# AOP_Decoupling.net
KiCad netlist of a schematic drawn in Altium Designer
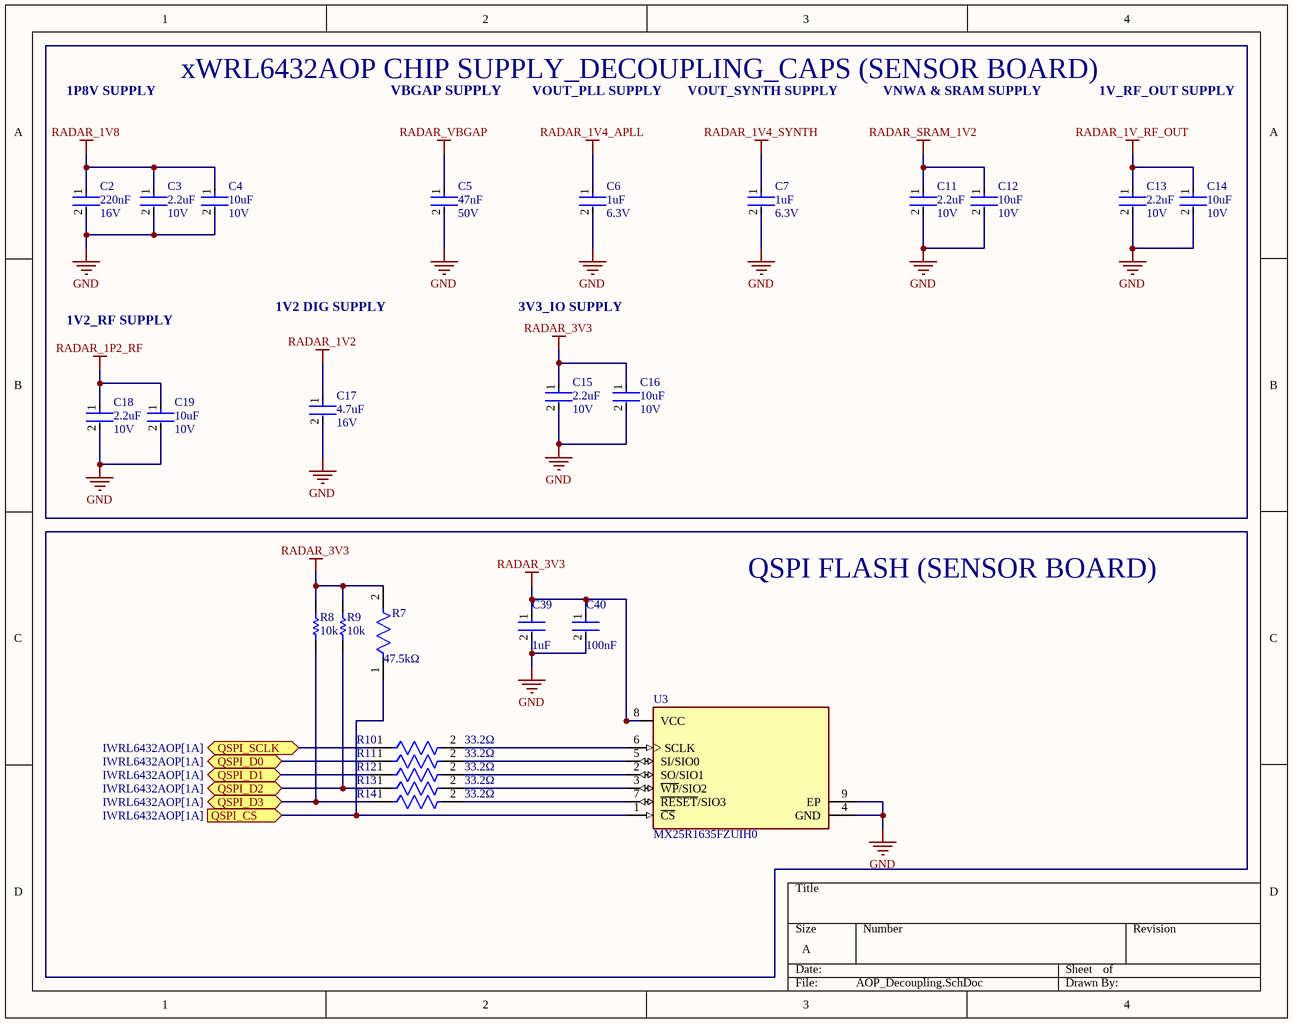
[diagram p0: AOP_Decoupling.SchDoc]

(export (version "E")
  (design (tool "Eeschema 10.0.6"))
  (components
    (comp (ref "C2")
      (value "GRM155R71C224KA12D")
      (footprint "FP-GRM155-0_05-IPC_C")
      (description "Chip Multilayer Ceramic Capacitors for General Purpose, 0402, 0.22uF, X7R, 15%, 10%, 16V")
      (fields
        (field (name "CAPACITANCE") "220nF")
        (field (name "VOLTAGE") "16V")
        (field (name "TOLERANCE") "10%")
      )
      (libsource (lib "Altium Content Vault") (part "02cd4be3c70576c341d710602a673aa"))
    )
    (comp (ref "C3")
      (value "GRM155R61A225ME01D")
      (footprint "FP-GRM155-0_05-IPC_A")
      (description "Chip Multilayer Ceramic Capacitors for General Purpose, 0402, 2.2uF, X5R, 15%, 20%, 10V")
      (fields (field (name "CAPACITANCE") "2.2uF") (field (name "VOLTAGE") "10V"))
      (libsource (lib "Altium Content Vault") (part "02cd4be3c70576c341d710602a673aa"))
    )
    (comp (ref "C4")
      (value "GRM188Z71A106MA73D")
      (footprint "FP-GRM188-0_2-IPC_B")
      (description "Chip Multilayer Ceramic Capacitors for General Purpose, 0603, 10uF, X7R, 15%, 20%, 10V")
      (fields (field (name "VOLTAGE") "10V") (field (name "CAPACITANCE") "10uF"))
      (libsource (lib "Altium Content Vault") (part "11868f565c42a9108669ba33697ecf6"))
    )
    (comp (ref "C5")
      (value "C1005X7R1H473K050BB")
      (footprint "FP-C1005-050-0_05-IPC_C")
      (description "Multilayer Ceramic Capacitors 47nF ±10% 50V X7R SMD 0402")
      (fields
        (field (name "VOLTAGE") "50V")
        (field (name "CAPACITANCE") "47nF")
        (field (name "VOLTAGE RATING (DC)") "50V")
        (field (name "TOLERANCE") "10%")
      )
      (libsource (lib "Altium Content Vault") (part "b4654b650e69147ec39a6b967a45e02"))
    )
    (comp (ref "C6")
      (value "GRM155R70J105KA12D")
      (footprint "FP-GRM155-0_05-MFG")
      (description "Chip Multilayer Ceramic Capacitors for General Purpose, 0402, 1.0uF, X7R, 15%, 10%, 6.3V")
      (fields
        (field (name "CAPACITANCE") "1uF")
        (field (name "TOLERANCE") "10%")
        (field (name "VOLTAGE RATING") "6.3V")
      )
      (libsource (lib "Altium Content Vault") (part "02cd4be3c70576c341d710602a673aa"))
    )
    (comp (ref "C7")
      (value "GRM155R70J105KA12D")
      (footprint "FP-GRM155-0_05-MFG")
      (description "Chip Multilayer Ceramic Capacitors for General Purpose, 0402, 1.0uF, X7R, 15%, 10%, 6.3V")
      (fields
        (field (name "CAPACITANCE") "1uF")
        (field (name "TOLERANCE") "10%")
        (field (name "VOLTAGE RATING") "6.3V")
      )
      (libsource (lib "Altium Content Vault") (part "02cd4be3c70576c341d710602a673aa"))
    )
    (comp (ref "C11")
      (value "GRM155R61A225ME01D")
      (footprint "FP-GRM155-0_05-IPC_A")
      (description "Chip Multilayer Ceramic Capacitors for General Purpose, 0402, 2.2uF, X5R, 15%, 20%, 10V")
      (fields (field (name "CAPACITANCE") "2.2uF") (field (name "VOLTAGE") "10V"))
      (libsource (lib "Altium Content Vault") (part "02cd4be3c70576c341d710602a673aa"))
    )
    (comp (ref "C12")
      (value "GRM188Z71A106MA73D")
      (footprint "FP-GRM188-0_2-IPC_B")
      (description "Chip Multilayer Ceramic Capacitors for General Purpose, 0603, 10uF, X7R, 15%, 20%, 10V")
      (fields (field (name "VOLTAGE") "10V") (field (name "CAPACITANCE") "10uF"))
      (libsource (lib "Altium Content Vault") (part "11868f565c42a9108669ba33697ecf6"))
    )
    (comp (ref "C13")
      (value "GRM155R61A225ME01D")
      (footprint "FP-GRM155-0_05-IPC_A")
      (description "Chip Multilayer Ceramic Capacitors for General Purpose, 0402, 2.2uF, X5R, 15%, 20%, 10V")
      (fields (field (name "CAPACITANCE") "2.2uF") (field (name "VOLTAGE") "10V"))
      (libsource (lib "Altium Content Vault") (part "02cd4be3c70576c341d710602a673aa"))
    )
    (comp (ref "C14")
      (value "GRM188Z71A106MA73D")
      (footprint "FP-GRM188-0_2-IPC_B")
      (description "Chip Multilayer Ceramic Capacitors for General Purpose, 0603, 10uF, X7R, 15%, 20%, 10V")
      (fields (field (name "VOLTAGE") "10V") (field (name "CAPACITANCE") "10uF"))
      (libsource (lib "Altium Content Vault") (part "11868f565c42a9108669ba33697ecf6"))
    )
    (comp (ref "C15")
      (value "GRM155R61A225ME01D")
      (footprint "FP-GRM155-0_05-IPC_A")
      (description "Chip Multilayer Ceramic Capacitors for General Purpose, 0402, 2.2uF, X5R, 15%, 20%, 10V")
      (fields (field (name "CAPACITANCE") "2.2uF") (field (name "VOLTAGE") "10V"))
      (libsource (lib "Altium Content Vault") (part "02cd4be3c70576c341d710602a673aa"))
    )
    (comp (ref "C16")
      (value "GRM188Z71A106MA73D")
      (footprint "FP-GRM188-0_2-IPC_B")
      (description "Chip Multilayer Ceramic Capacitors for General Purpose, 0603, 10uF, X7R, 15%, 20%, 10V")
      (fields (field (name "VOLTAGE") "10V") (field (name "CAPACITANCE") "10uF"))
      (libsource (lib "Altium Content Vault") (part "11868f565c42a9108669ba33697ecf6"))
    )
    (comp (ref "C17")
      (value "GCJ21BR71C475KA01L")
      (footprint "FP-GCJ21B-0_3-IPC_C")
      (description "Multilayer Ceramic Capacitors MLCC - SMD/SMT 0805 4.7uF 10%, 16VDC,  X7R 15%")
      (fields
        (field (name "VOLTAGE RATING (DC)") "16V")
        (field (name "CAPACITANCE") "4.7uF")
        (field (name "TOLERANCE") "10%")
      )
      (libsource (lib "Altium Content Vault") (part "02cd4be3c70576c341d710602a673aa"))
    )
    (comp (ref "C18")
      (value "GRM155R61A225ME01D")
      (footprint "FP-GRM155-0_05-IPC_A")
      (description "Chip Multilayer Ceramic Capacitors for General Purpose, 0402, 2.2uF, X5R, 15%, 20%, 10V")
      (fields (field (name "CAPACITANCE") "2.2uF") (field (name "VOLTAGE") "10V"))
      (libsource (lib "Altium Content Vault") (part "02cd4be3c70576c341d710602a673aa"))
    )
    (comp (ref "C19")
      (value "GRM188Z71A106MA73D")
      (footprint "FP-GRM188-0_2-IPC_B")
      (description "Chip Multilayer Ceramic Capacitors for General Purpose, 0603, 10uF, X7R, 15%, 20%, 10V")
      (fields (field (name "VOLTAGE") "10V") (field (name "CAPACITANCE") "10uF"))
      (libsource (lib "Altium Content Vault") (part "11868f565c42a9108669ba33697ecf6"))
    )
    (comp (ref "C39")
      (value "GRM155C80J105KA12D")
      (footprint "FP-GRM155-0_05-IPC_C")
      (description "Chip Multilayer Ceramic Capacitors for General Purpose, 0402, 1.0uF, X6S, 22%, 10%, 6.3V")
      (fields (field (name "CAPACITANCE") "1uF") (field (name "TOLERANCE") "10%"))
      (libsource (lib "Altium Content Vault") (part "02cd4be3c70576c341d710602a673aa"))
    )
    (comp (ref "C40")
      (value "C1005X7R1H104K050BE")
      (footprint "FP-C1005-050-IPC_C")
      (description "CAP CER 0.1UF 50V X7R 0402")
      (fields (field (name "TOLERANCE") "10%") (field (name "CAPACITANCE") "100nF"))
      (libsource (lib "Altium Content Vault") (part "b4654b650e69147ec39a6b967a45e02"))
    )
    (comp (ref "R7")
      (value "RC0402FR-1047K5L")
      (footprint "FP-RC0402-0_4-MFG")
      (description "RC0402FR-1047K5L General Purpose Chip Resistor Thick Film 0402 47.5kOhm 1% Paper T/R")
      (fields (field (name "RESISTANCE") "47.5kΩ") (field (name "TOLERANCE") "1%"))
      (libsource (lib "Altium Content Vault") (part "1029c3af85768c4190bb7ad29bc67b5"))
    )
    (comp (ref "R8")
      (value "10k")
      (footprint "RESC1005X40X25LL05T10")
      (fields (field (name "PART NUMBER") "RC0402FR-0710KL") (field (name "MANUFACTURER") "Yageo / Phycomp"))
      (libsource (lib "Altium Content Vault") (part "RES"))
    )
    (comp (ref "R9")
      (value "10k")
      (footprint "RESC1005X40X25LL05T10")
      (fields (field (name "PART NUMBER") "RC0402FR-0710KL") (field (name "MANUFACTURER") "Yageo / Phycomp"))
      (libsource (lib "Altium Content Vault") (part "RES"))
    )
    (comp (ref "R10")
      (value "RT0402FRE0733R2L")
      (footprint "FP-RT0402-0_35-MFG")
      (fields (field (name "TOLERANCE") "1%") (field (name "RESISTANCE") "33.2Ω"))
      (libsource (lib "Altium Content Vault") (part "1029c3af85768c4190bb7ad29bc67b5"))
    )
    (comp (ref "R11")
      (value "RT0402FRE0733R2L")
      (footprint "FP-RT0402-0_35-MFG")
      (fields (field (name "TOLERANCE") "1%") (field (name "RESISTANCE") "33.2Ω"))
      (libsource (lib "Altium Content Vault") (part "1029c3af85768c4190bb7ad29bc67b5"))
    )
    (comp (ref "R12")
      (value "RT0402FRE0733R2L")
      (footprint "FP-RT0402-0_35-MFG")
      (fields (field (name "TOLERANCE") "1%") (field (name "RESISTANCE") "33.2Ω"))
      (libsource (lib "Altium Content Vault") (part "1029c3af85768c4190bb7ad29bc67b5"))
    )
    (comp (ref "R13")
      (value "RT0402FRE0733R2L")
      (footprint "FP-RT0402-0_35-MFG")
      (fields (field (name "TOLERANCE") "1%") (field (name "RESISTANCE") "33.2Ω"))
      (libsource (lib "Altium Content Vault") (part "1029c3af85768c4190bb7ad29bc67b5"))
    )
    (comp (ref "R14")
      (value "RT0402FRE0733R2L")
      (footprint "FP-RT0402-0_35-MFG")
      (fields (field (name "TOLERANCE") "1%") (field (name "RESISTANCE") "33.2Ω"))
      (libsource (lib "Altium Content Vault") (part "1029c3af85768c4190bb7ad29bc67b5"))
    )
    (comp (ref "U3")
      (value "MX25R1635FZUIH0")
      (footprint "FP-USON-8-2x3mm-MFG")
      (description "IC FLASH 16M SPI 80MHZ 8USON")
      (libsource (lib "Altium Content Vault") (part "cd154f7aea21c8d18e316dcfc16d813"))
    )
  )
  (nets
    (net (code "1") (name "/QSPI_CS") (class "Default")
      (node (ref "R7") (pin "1") (pinfunction "1_1") (pintype "passive"))
      (node (ref "U3") (pin "1") (pinfunction "~{CS}_1") (pintype "input"))
    )
    (net (code "2") (name "/QSPI_D0") (class "Default")
      (node (ref "R11") (pin "1") (pinfunction "1_1") (pintype "passive"))
    )
    (net (code "3") (name "/QSPI_D1") (class "Default")
      (node (ref "R12") (pin "1") (pinfunction "1_1") (pintype "passive"))
    )
    (net (code "4") (name "/QSPI_D2") (class "Default")
      (node (ref "R13") (pin "1") (pinfunction "1_1") (pintype "passive"))
      (node (ref "R9") (pin "1") (pinfunction "1_1") (pintype "passive"))
    )
    (net (code "5") (name "/QSPI_D3") (class "Default")
      (node (ref "R14") (pin "1") (pinfunction "1_1") (pintype "passive"))
      (node (ref "R8") (pin "1") (pinfunction "1_1") (pintype "passive"))
    )
    (net (code "6") (name "/QSPI_SCLK") (class "Default")
      (node (ref "R10") (pin "1") (pinfunction "1_1") (pintype "passive"))
    )
    (net (code "7") (name "GND") (class "Default")
      (node (ref "C11") (pin "2") (pinfunction "2_2") (pintype "passive"))
      (node (ref "C12") (pin "2") (pinfunction "2_2") (pintype "passive"))
      (node (ref "C13") (pin "2") (pinfunction "2_2") (pintype "passive"))
      (node (ref "C14") (pin "2") (pinfunction "2_2") (pintype "passive"))
      (node (ref "C15") (pin "2") (pinfunction "2_2") (pintype "passive"))
      (node (ref "C16") (pin "2") (pinfunction "2_2") (pintype "passive"))
      (node (ref "C17") (pin "2") (pinfunction "2_2") (pintype "passive"))
      (node (ref "C18") (pin "2") (pinfunction "2_2") (pintype "passive"))
      (node (ref "C19") (pin "2") (pinfunction "2_2") (pintype "passive"))
      (node (ref "C2") (pin "2") (pinfunction "2_2") (pintype "passive"))
      (node (ref "C3") (pin "2") (pinfunction "2_2") (pintype "passive"))
      (node (ref "C39") (pin "2") (pinfunction "2_2") (pintype "passive"))
      (node (ref "C4") (pin "2") (pinfunction "2_2") (pintype "passive"))
      (node (ref "C40") (pin "2") (pinfunction "2_2") (pintype "passive"))
      (node (ref "C5") (pin "2") (pinfunction "2_2") (pintype "passive"))
      (node (ref "C6") (pin "2") (pinfunction "2_2") (pintype "passive"))
      (node (ref "C7") (pin "2") (pinfunction "2_2") (pintype "passive"))
      (node (ref "U3") (pin "4") (pinfunction "GND_4") (pintype "power_in"))
      (node (ref "U3") (pin "9") (pinfunction "EP_9") (pintype "passive"))
    )
    (net (code "8") (name "Net-(U3-SCLK)") (class "Default")
      (node (ref "R10") (pin "2") (pinfunction "2_2") (pintype "passive"))
      (node (ref "U3") (pin "6") (pinfunction "SCLK_6") (pintype "input"))
    )
    (net (code "9") (name "Net-(U3-SI{slash}SIO0)") (class "Default")
      (node (ref "R11") (pin "2") (pinfunction "2_2") (pintype "passive"))
      (node (ref "U3") (pin "5") (pinfunction "SI/SIO0_5") (pintype "bidirectional"))
    )
    (net (code "10") (name "Net-(U3-SO{slash}SIO1)") (class "Default")
      (node (ref "R12") (pin "2") (pinfunction "2_2") (pintype "passive"))
      (node (ref "U3") (pin "2") (pinfunction "SO/SIO1_2") (pintype "bidirectional"))
    )
    (net (code "11") (name "Net-(U3-~{RESET}{slash}SIO3)") (class "Default")
      (node (ref "R14") (pin "2") (pinfunction "2_2") (pintype "passive"))
      (node (ref "U3") (pin "7") (pinfunction "~{RESET}/SIO3_7") (pintype "bidirectional"))
    )
    (net (code "12") (name "Net-(U3-~{WP}{slash}SIO2)") (class "Default")
      (node (ref "R13") (pin "2") (pinfunction "2_2") (pintype "passive"))
      (node (ref "U3") (pin "3") (pinfunction "~{WP}/SIO2_3") (pintype "bidirectional"))
    )
    (net (code "13") (name "RADAR_1P2_RF") (class "Default")
      (node (ref "C18") (pin "1") (pinfunction "1_1") (pintype "passive"))
      (node (ref "C19") (pin "1") (pinfunction "1_1") (pintype "passive"))
    )
    (net (code "14") (name "RADAR_1V2") (class "Default")
      (node (ref "C17") (pin "1") (pinfunction "1_1") (pintype "passive"))
    )
    (net (code "15") (name "RADAR_1V4_APLL") (class "Default")
      (node (ref "C6") (pin "1") (pinfunction "1_1") (pintype "passive"))
    )
    (net (code "16") (name "RADAR_1V4_SYNTH") (class "Default")
      (node (ref "C7") (pin "1") (pinfunction "1_1") (pintype "passive"))
    )
    (net (code "17") (name "RADAR_1V8") (class "Default")
      (node (ref "C2") (pin "1") (pinfunction "1_1") (pintype "passive"))
      (node (ref "C3") (pin "1") (pinfunction "1_1") (pintype "passive"))
      (node (ref "C4") (pin "1") (pinfunction "1_1") (pintype "passive"))
    )
    (net (code "18") (name "RADAR_1V_RF_OUT") (class "Default")
      (node (ref "C13") (pin "1") (pinfunction "1_1") (pintype "passive"))
      (node (ref "C14") (pin "1") (pinfunction "1_1") (pintype "passive"))
    )
    (net (code "19") (name "RADAR_3V3") (class "Default")
      (node (ref "C15") (pin "1") (pinfunction "1_1") (pintype "passive"))
      (node (ref "C16") (pin "1") (pinfunction "1_1") (pintype "passive"))
      (node (ref "C39") (pin "1") (pinfunction "1_1") (pintype "passive"))
      (node (ref "C40") (pin "1") (pinfunction "1_1") (pintype "passive"))
      (node (ref "R7") (pin "2") (pinfunction "2_2") (pintype "passive"))
      (node (ref "R8") (pin "2") (pinfunction "2_2") (pintype "passive"))
      (node (ref "R9") (pin "2") (pinfunction "2_2") (pintype "passive"))
      (node (ref "U3") (pin "8") (pinfunction "VCC_8") (pintype "power_in"))
    )
    (net (code "20") (name "RADAR_SRAM_1V2") (class "Default")
      (node (ref "C11") (pin "1") (pinfunction "1_1") (pintype "passive"))
      (node (ref "C12") (pin "1") (pinfunction "1_1") (pintype "passive"))
    )
    (net (code "21") (name "RADAR_VBGAP") (class "Default")
      (node (ref "C5") (pin "1") (pinfunction "1_1") (pintype "passive"))
    )
  )
)
